# test.net
KiCad netlist of a schematic drawn in EAGLE
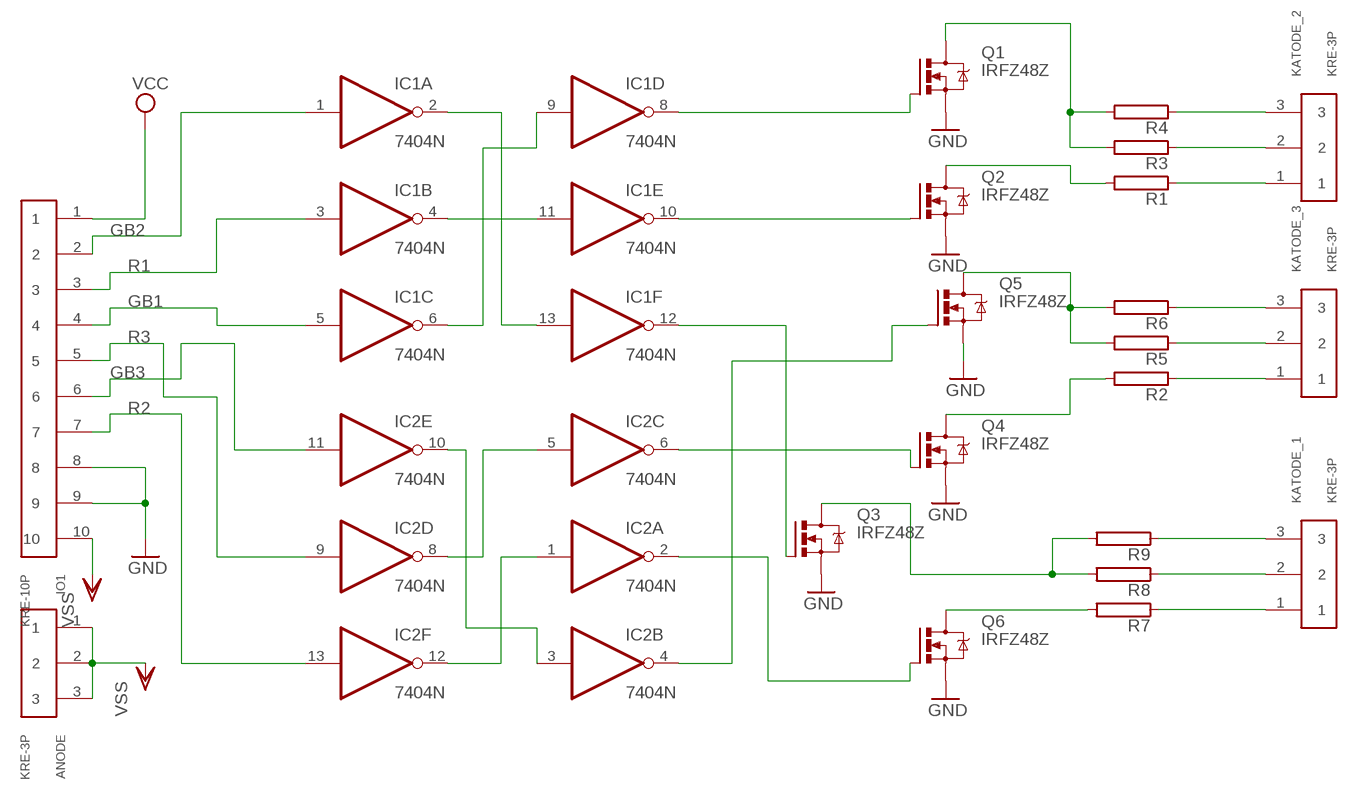
[diagram p0: schematic, sheet 1]

(export (version "E")
  (design (tool "Eeschema 10.0.6"))
  (components
    (comp (ref "ANODE")
      (value "KRE-3P")
      (footprint "eagle-import:KRE-3P")
      (libsource (lib "eagle-import") (part "KRE-3P"))
    )
    (comp (ref "IC1")
      (value "7404N")
      (footprint "eagle-import:DIL14")
      (libsource (lib "eagle-import") (part "7404N"))
    )
    (comp (ref "IC2")
      (value "7404N")
      (footprint "eagle-import:DIL14")
      (libsource (lib "eagle-import") (part "7404N"))
    )
    (comp (ref "IO1")
      (value "KRE-10P")
      (footprint "eagle-import:KRE-10P")
      (libsource (lib "eagle-import") (part "KRE-10P"))
    )
    (comp (ref "KATODE_1")
      (value "KRE-3P")
      (footprint "eagle-import:KRE-3P")
      (libsource (lib "eagle-import") (part "KRE-3P"))
    )
    (comp (ref "KATODE_2")
      (value "KRE-3P")
      (footprint "eagle-import:KRE-3P")
      (libsource (lib "eagle-import") (part "KRE-3P"))
    )
    (comp (ref "KATODE_3")
      (value "KRE-3P")
      (footprint "eagle-import:KRE-3P")
      (libsource (lib "eagle-import") (part "KRE-3P"))
    )
    (comp (ref "Q1")
      (value "IRFZ48Z")
      (footprint "eagle-import:TO220BH")
      (libsource (lib "eagle-import") (part "IRFZ48Z"))
    )
    (comp (ref "Q2")
      (value "IRFZ48Z")
      (footprint "eagle-import:TO220BH")
      (libsource (lib "eagle-import") (part "IRFZ48Z"))
    )
    (comp (ref "Q3")
      (value "IRFZ48Z")
      (footprint "eagle-import:TO220BH")
      (libsource (lib "eagle-import") (part "IRFZ48Z"))
    )
    (comp (ref "Q4")
      (value "IRFZ48Z")
      (footprint "eagle-import:TO220BH")
      (libsource (lib "eagle-import") (part "IRFZ48Z"))
    )
    (comp (ref "Q5")
      (value "IRFZ48Z")
      (footprint "eagle-import:TO220BH")
      (libsource (lib "eagle-import") (part "IRFZ48Z"))
    )
    (comp (ref "Q6")
      (value "IRFZ48Z")
      (footprint "eagle-import:TO220BH")
      (libsource (lib "eagle-import") (part "IRFZ48Z"))
    )
    (comp (ref "R1")
      (value "RAC10")
      (footprint "eagle-import:AC10")
      (libsource (lib "eagle-import") (part "RAC10"))
    )
    (comp (ref "R2")
      (value "RAC10")
      (footprint "eagle-import:AC10")
      (libsource (lib "eagle-import") (part "RAC10"))
    )
    (comp (ref "R3")
      (value "RAC10")
      (footprint "eagle-import:AC10")
      (libsource (lib "eagle-import") (part "RAC10"))
    )
    (comp (ref "R4")
      (value "RAC10")
      (footprint "eagle-import:AC10")
      (libsource (lib "eagle-import") (part "RAC10"))
    )
    (comp (ref "R5")
      (value "RAC10")
      (footprint "eagle-import:AC10")
      (libsource (lib "eagle-import") (part "RAC10"))
    )
    (comp (ref "R6")
      (value "RAC10")
      (footprint "eagle-import:AC10")
      (libsource (lib "eagle-import") (part "RAC10"))
    )
    (comp (ref "R7")
      (value "RAC10")
      (footprint "eagle-import:AC10")
      (libsource (lib "eagle-import") (part "RAC10"))
    )
    (comp (ref "R8")
      (value "RAC10")
      (footprint "eagle-import:AC10")
      (libsource (lib "eagle-import") (part "RAC10"))
    )
    (comp (ref "R9")
      (value "RAC10")
      (footprint "eagle-import:AC10")
      (libsource (lib "eagle-import") (part "RAC10"))
    )
  )
  (nets
    (net (code "1") (name "/GB1") (class "Default")
      (node (ref "IC1") (pin "5") (pinfunction "I_5") (pintype "input"))
      (node (ref "IO1") (pin "4") (pinfunction "4_4") (pintype "bidirectional"))
    )
    (net (code "2") (name "/GB2") (class "Default")
      (node (ref "IC1") (pin "1") (pinfunction "I_1") (pintype "input"))
      (node (ref "IO1") (pin "2") (pinfunction "2_2") (pintype "bidirectional"))
    )
    (net (code "3") (name "/GB3") (class "Default")
      (node (ref "IC2") (pin "11") (pinfunction "I_11") (pintype "input"))
      (node (ref "IO1") (pin "6") (pinfunction "6_6") (pintype "bidirectional"))
    )
    (net (code "4") (name "/R1") (class "Default")
      (node (ref "IC1") (pin "3") (pinfunction "I_3") (pintype "input"))
      (node (ref "IO1") (pin "3") (pinfunction "3_3") (pintype "bidirectional"))
    )
    (net (code "5") (name "/R2") (class "Default")
      (node (ref "IC2") (pin "13") (pinfunction "I_13") (pintype "input"))
      (node (ref "IO1") (pin "7") (pinfunction "7_7") (pintype "bidirectional"))
    )
    (net (code "6") (name "/R3") (class "Default")
      (node (ref "IC2") (pin "9") (pinfunction "I_9") (pintype "input"))
      (node (ref "IO1") (pin "5") (pinfunction "5_5") (pintype "bidirectional"))
    )
    (net (code "7") (name "GND") (class "Default")
      (node (ref "IO1") (pin "8") (pinfunction "8_8") (pintype "bidirectional"))
      (node (ref "IO1") (pin "9") (pinfunction "9_9") (pintype "bidirectional"))
      (node (ref "Q1") (pin "S") (pinfunction "S_S") (pintype "passive"))
      (node (ref "Q2") (pin "S") (pinfunction "S_S") (pintype "passive"))
      (node (ref "Q3") (pin "S") (pinfunction "S_S") (pintype "passive"))
      (node (ref "Q4") (pin "S") (pinfunction "S_S") (pintype "passive"))
      (node (ref "Q5") (pin "S") (pinfunction "S_S") (pintype "passive"))
      (node (ref "Q6") (pin "S") (pinfunction "S_S") (pintype "passive"))
    )
    (net (code "8") (name "Net-(IC1A-O)") (class "Default")
      (node (ref "IC1") (pin "13") (pinfunction "I_13") (pintype "input"))
      (node (ref "IC1") (pin "2") (pinfunction "O_2") (pintype "output"))
    )
    (net (code "9") (name "Net-(IC1B-O)") (class "Default")
      (node (ref "IC1") (pin "11") (pinfunction "I_11") (pintype "input"))
      (node (ref "IC1") (pin "4") (pinfunction "O_4") (pintype "output"))
    )
    (net (code "10") (name "Net-(IC1C-O)") (class "Default")
      (node (ref "IC1") (pin "6") (pinfunction "O_6") (pintype "output"))
      (node (ref "IC1") (pin "9") (pinfunction "I_9") (pintype "input"))
    )
    (net (code "11") (name "Net-(IC1D-O)") (class "Default")
      (node (ref "IC1") (pin "8") (pinfunction "O_8") (pintype "output"))
      (node (ref "Q1") (pin "G") (pinfunction "G_G") (pintype "passive"))
    )
    (net (code "12") (name "Net-(IC1E-O)") (class "Default")
      (node (ref "IC1") (pin "10") (pinfunction "O_10") (pintype "output"))
      (node (ref "Q2") (pin "G") (pinfunction "G_G") (pintype "passive"))
    )
    (net (code "13") (name "Net-(IC1F-O)") (class "Default")
      (node (ref "IC1") (pin "12") (pinfunction "O_12") (pintype "output"))
      (node (ref "Q3") (pin "G") (pinfunction "G_G") (pintype "passive"))
    )
    (net (code "14") (name "Net-(IC2A-I)") (class "Default")
      (node (ref "IC2") (pin "1") (pinfunction "I_1") (pintype "input"))
      (node (ref "IC2") (pin "12") (pinfunction "O_12") (pintype "output"))
    )
    (net (code "15") (name "Net-(IC2A-O)") (class "Default")
      (node (ref "IC2") (pin "2") (pinfunction "O_2") (pintype "output"))
      (node (ref "Q6") (pin "G") (pinfunction "G_G") (pintype "passive"))
    )
    (net (code "16") (name "Net-(IC2B-I)") (class "Default")
      (node (ref "IC2") (pin "10") (pinfunction "O_10") (pintype "output"))
      (node (ref "IC2") (pin "3") (pinfunction "I_3") (pintype "input"))
    )
    (net (code "17") (name "Net-(IC2B-O)") (class "Default")
      (node (ref "IC2") (pin "4") (pinfunction "O_4") (pintype "output"))
      (node (ref "Q5") (pin "G") (pinfunction "G_G") (pintype "passive"))
    )
    (net (code "18") (name "Net-(IC2C-I)") (class "Default")
      (node (ref "IC2") (pin "5") (pinfunction "I_5") (pintype "input"))
      (node (ref "IC2") (pin "8") (pinfunction "O_8") (pintype "output"))
    )
    (net (code "19") (name "Net-(IC2C-O)") (class "Default")
      (node (ref "IC2") (pin "6") (pinfunction "O_6") (pintype "output"))
      (node (ref "Q4") (pin "G") (pinfunction "G_G") (pintype "passive"))
    )
    (net (code "20") (name "Net-(KATODE_1-Pad1)") (class "Default")
      (node (ref "KATODE_1") (pin "1") (pinfunction "1_1") (pintype "bidirectional"))
      (node (ref "R7") (pin "1") (pinfunction "1_1") (pintype "passive"))
    )
    (net (code "21") (name "Net-(KATODE_1-Pad2)") (class "Default")
      (node (ref "KATODE_1") (pin "2") (pinfunction "2_2") (pintype "bidirectional"))
      (node (ref "R8") (pin "1") (pinfunction "1_1") (pintype "passive"))
    )
    (net (code "22") (name "Net-(KATODE_1-Pad3)") (class "Default")
      (node (ref "KATODE_1") (pin "3") (pinfunction "3_3") (pintype "bidirectional"))
      (node (ref "R9") (pin "1") (pinfunction "1_1") (pintype "passive"))
    )
    (net (code "23") (name "Net-(KATODE_2-Pad1)") (class "Default")
      (node (ref "KATODE_2") (pin "1") (pinfunction "1_1") (pintype "bidirectional"))
      (node (ref "R1") (pin "1") (pinfunction "1_1") (pintype "passive"))
    )
    (net (code "24") (name "Net-(KATODE_2-Pad2)") (class "Default")
      (node (ref "KATODE_2") (pin "2") (pinfunction "2_2") (pintype "bidirectional"))
      (node (ref "R3") (pin "1") (pinfunction "1_1") (pintype "passive"))
    )
    (net (code "25") (name "Net-(KATODE_2-Pad3)") (class "Default")
      (node (ref "KATODE_2") (pin "3") (pinfunction "3_3") (pintype "bidirectional"))
      (node (ref "R4") (pin "1") (pinfunction "1_1") (pintype "passive"))
    )
    (net (code "26") (name "Net-(KATODE_3-Pad1)") (class "Default")
      (node (ref "KATODE_3") (pin "1") (pinfunction "1_1") (pintype "bidirectional"))
      (node (ref "R2") (pin "1") (pinfunction "1_1") (pintype "passive"))
    )
    (net (code "27") (name "Net-(KATODE_3-Pad2)") (class "Default")
      (node (ref "KATODE_3") (pin "2") (pinfunction "2_2") (pintype "bidirectional"))
      (node (ref "R5") (pin "1") (pinfunction "1_1") (pintype "passive"))
    )
    (net (code "28") (name "Net-(KATODE_3-Pad3)") (class "Default")
      (node (ref "KATODE_3") (pin "3") (pinfunction "3_3") (pintype "bidirectional"))
      (node (ref "R6") (pin "1") (pinfunction "1_1") (pintype "passive"))
    )
    (net (code "29") (name "Net-(Q1-PadD)") (class "Default")
      (node (ref "Q1") (pin "D") (pinfunction "D_D") (pintype "passive"))
      (node (ref "R3") (pin "2") (pinfunction "2_2") (pintype "passive"))
      (node (ref "R4") (pin "2") (pinfunction "2_2") (pintype "passive"))
    )
    (net (code "30") (name "Net-(Q2-PadD)") (class "Default")
      (node (ref "Q2") (pin "D") (pinfunction "D_D") (pintype "passive"))
      (node (ref "R1") (pin "2") (pinfunction "2_2") (pintype "passive"))
    )
    (net (code "31") (name "Net-(Q3-PadD)") (class "Default")
      (node (ref "Q3") (pin "D") (pinfunction "D_D") (pintype "passive"))
      (node (ref "R8") (pin "2") (pinfunction "2_2") (pintype "passive"))
      (node (ref "R9") (pin "2") (pinfunction "2_2") (pintype "passive"))
    )
    (net (code "32") (name "Net-(Q4-PadD)") (class "Default")
      (node (ref "Q4") (pin "D") (pinfunction "D_D") (pintype "passive"))
      (node (ref "R2") (pin "2") (pinfunction "2_2") (pintype "passive"))
    )
    (net (code "33") (name "Net-(Q5-PadD)") (class "Default")
      (node (ref "Q5") (pin "D") (pinfunction "D_D") (pintype "passive"))
      (node (ref "R5") (pin "2") (pinfunction "2_2") (pintype "passive"))
      (node (ref "R6") (pin "2") (pinfunction "2_2") (pintype "passive"))
    )
    (net (code "34") (name "Net-(Q6-PadD)") (class "Default")
      (node (ref "Q6") (pin "D") (pinfunction "D_D") (pintype "passive"))
      (node (ref "R7") (pin "2") (pinfunction "2_2") (pintype "passive"))
    )
    (net (code "35") (name "VCC") (class "Default")
      (node (ref "IO1") (pin "1") (pinfunction "1_1") (pintype "bidirectional"))
    )
    (net (code "36") (name "VSS") (class "Default")
      (node (ref "ANODE") (pin "1") (pinfunction "1_1") (pintype "bidirectional"))
      (node (ref "ANODE") (pin "2") (pinfunction "2_2") (pintype "bidirectional"))
      (node (ref "ANODE") (pin "3") (pinfunction "3_3") (pintype "bidirectional"))
      (node (ref "IO1") (pin "10") (pinfunction "10_10") (pintype "bidirectional"))
    )
  )
)
